# CAN_Wake_Up.net
KiCad netlist of a schematic drawn in EAGLE
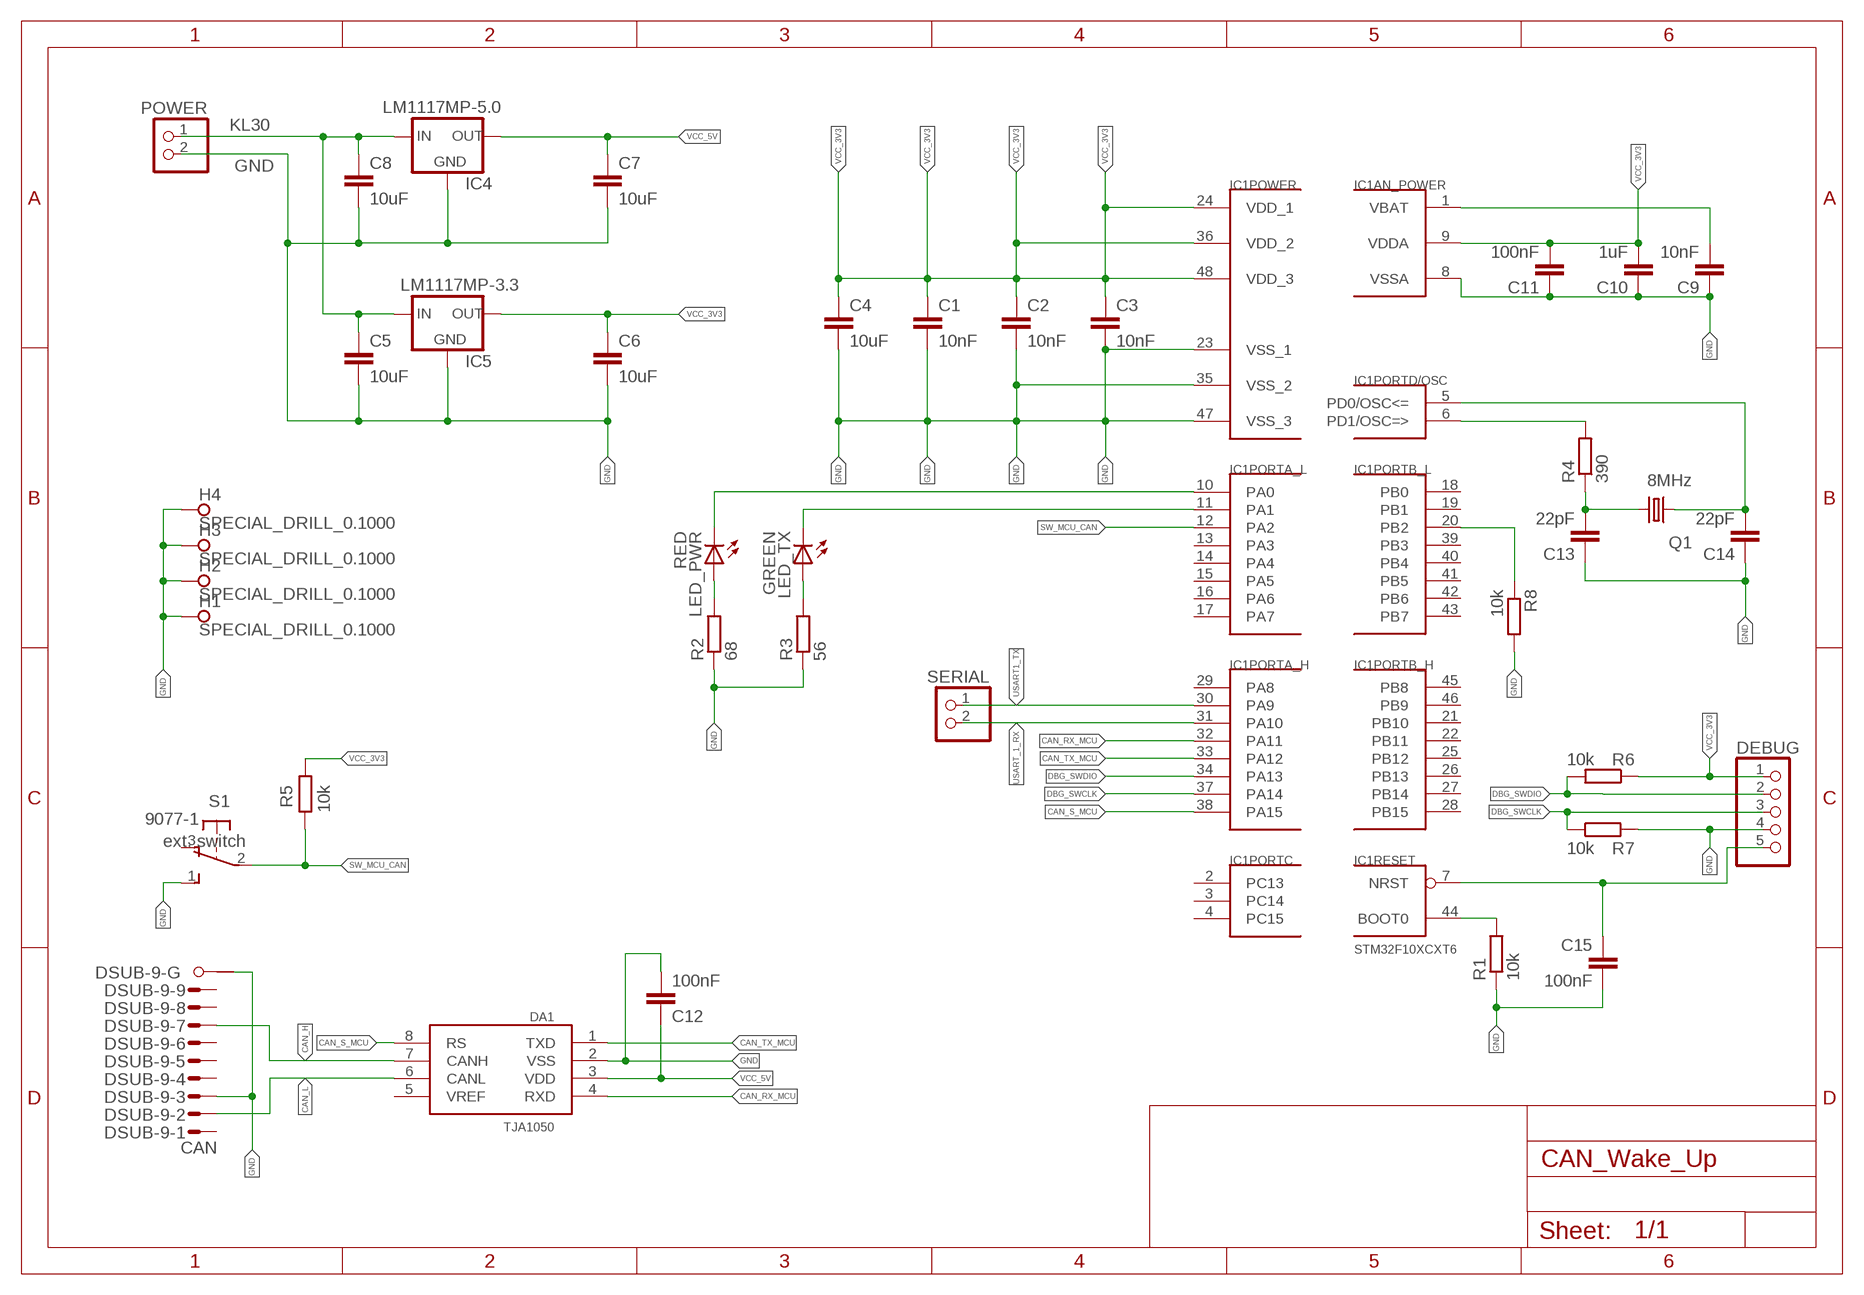
[diagram p0: schematic, sheet 1]

(export (version "E")
  (design (tool "Eeschema 10.0.6"))
  (components
    (comp (ref "C1")
      (value "10nF")
      (footprint "eagle-import:C0805")
      (libsource (lib "eagle-import") (part "C-EUC0805"))
    )
    (comp (ref "C2")
      (value "10nF")
      (footprint "eagle-import:C0805")
      (libsource (lib "eagle-import") (part "C-EUC0805"))
    )
    (comp (ref "C3")
      (value "10nF")
      (footprint "eagle-import:C0805")
      (libsource (lib "eagle-import") (part "C-EUC0805"))
    )
    (comp (ref "C4")
      (value "10uF")
      (footprint "eagle-import:C0805")
      (libsource (lib "eagle-import") (part "C-EUC0805"))
    )
    (comp (ref "C5")
      (value "10uF")
      (footprint "eagle-import:C0805")
      (libsource (lib "eagle-import") (part "C-EUC0805"))
    )
    (comp (ref "C6")
      (value "10uF")
      (footprint "eagle-import:C0805")
      (libsource (lib "eagle-import") (part "C-EUC0805"))
    )
    (comp (ref "C7")
      (value "10uF")
      (footprint "eagle-import:C0805")
      (libsource (lib "eagle-import") (part "C-EUC0805"))
    )
    (comp (ref "C8")
      (value "10uF")
      (footprint "eagle-import:C0805")
      (libsource (lib "eagle-import") (part "C-EUC0805"))
    )
    (comp (ref "C9")
      (value "10nF")
      (footprint "eagle-import:C0805")
      (libsource (lib "eagle-import") (part "C-EUC0805"))
    )
    (comp (ref "C10")
      (value "1uF")
      (footprint "eagle-import:C0805")
      (libsource (lib "eagle-import") (part "C-EUC0805"))
    )
    (comp (ref "C11")
      (value "100nF")
      (footprint "eagle-import:C0805")
      (libsource (lib "eagle-import") (part "C-EUC0805"))
    )
    (comp (ref "C12")
      (value "100nF")
      (footprint "eagle-import:C0805")
      (libsource (lib "eagle-import") (part "C-EUC0805"))
    )
    (comp (ref "C13")
      (value "22pF")
      (footprint "eagle-import:C0805")
      (libsource (lib "eagle-import") (part "C-EUC0805"))
    )
    (comp (ref "C14")
      (value "22pF")
      (footprint "eagle-import:C0805")
      (libsource (lib "eagle-import") (part "C-EUC0805"))
    )
    (comp (ref "C15")
      (value "100nF")
      (footprint "eagle-import:C0805")
      (libsource (lib "eagle-import") (part "C-EUC0805"))
    )
    (comp (ref "DA1")
      (value "TJA1050")
      (footprint "eagle-import:SO08")
      (libsource (lib "eagle-import") (part "TJA1050"))
    )
    (comp (ref "DEBUG")
      (value "PINHD-1X5")
      (footprint "eagle-import:1X05")
      (libsource (lib "eagle-import") (part "PINHD-1X5"))
    )
    (comp (ref "DSUB-9")
      (value "CAN")
      (footprint "eagle-import:M09HP")
      (libsource (lib "eagle-import") (part "M09HPS"))
    )
    (comp (ref "H1")
      (value "SPECIAL_DRILL_0.1000")
      (footprint "eagle-import:PAD_0.1000")
      (libsource (lib "eagle-import") (part "SPECIAL_DRILL_0.1000"))
    )
    (comp (ref "H2")
      (value "SPECIAL_DRILL_0.1000")
      (footprint "eagle-import:PAD_0.1000")
      (libsource (lib "eagle-import") (part "SPECIAL_DRILL_0.1000"))
    )
    (comp (ref "H3")
      (value "SPECIAL_DRILL_0.1000")
      (footprint "eagle-import:PAD_0.1000")
      (libsource (lib "eagle-import") (part "SPECIAL_DRILL_0.1000"))
    )
    (comp (ref "H4")
      (value "SPECIAL_DRILL_0.1000")
      (footprint "eagle-import:PAD_0.1000")
      (libsource (lib "eagle-import") (part "SPECIAL_DRILL_0.1000"))
    )
    (comp (ref "IC1")
      (value "STM32F10XCXT6")
      (footprint "eagle-import:TQFP48")
      (libsource (lib "eagle-import") (part "STM32F10XCXT6"))
    )
    (comp (ref "IC4")
      (value "LM1117MP-5.0")
      (footprint "eagle-import:SOT223")
      (fields (field (name "MF") "Texas Instruments"))
      (libsource (lib "eagle-import") (part "LM1117?-MP5.0"))
    )
    (comp (ref "IC5")
      (value "LM1117MP-3.3")
      (footprint "eagle-import:SOT223")
      (fields (field (name "MF") "Texas Instruments"))
      (libsource (lib "eagle-import") (part "LM1117?-MP3.3"))
    )
    (comp (ref "LED_PWR")
      (value "RED")
      (footprint "eagle-import:SML0805")
      (libsource (lib "eagle-import") (part "LEDSML0805"))
    )
    (comp (ref "LED_TX")
      (value "GREEN")
      (footprint "eagle-import:SML0805")
      (libsource (lib "eagle-import") (part "LEDSML0805"))
    )
    (comp (ref "POWER")
      (value "PINHD-1X2")
      (footprint "eagle-import:1X02")
      (libsource (lib "eagle-import") (part "PINHD-1X2"))
    )
    (comp (ref "Q1")
      (value "8MHz")
      (footprint "eagle-import:HC49UP")
      (libsource (lib "eagle-import") (part "CRYSTALHC49UP"))
    )
    (comp (ref "R1")
      (value "10k")
      (footprint "eagle-import:R0805")
      (libsource (lib "eagle-import") (part "R-EU_R0805"))
    )
    (comp (ref "R2")
      (value "68")
      (footprint "eagle-import:R0805")
      (libsource (lib "eagle-import") (part "R-EU_R0805"))
    )
    (comp (ref "R3")
      (value "56")
      (footprint "eagle-import:R0805")
      (libsource (lib "eagle-import") (part "R-EU_R0805"))
    )
    (comp (ref "R4")
      (value "390")
      (footprint "eagle-import:R0805")
      (libsource (lib "eagle-import") (part "R-EU_R0805"))
    )
    (comp (ref "R5")
      (value "10k")
      (footprint "eagle-import:R0805")
      (libsource (lib "eagle-import") (part "R-EU_R0805"))
    )
    (comp (ref "R6")
      (value "10k")
      (footprint "eagle-import:R0805")
      (libsource (lib "eagle-import") (part "R-EU_R0805"))
    )
    (comp (ref "R7")
      (value "10k")
      (footprint "eagle-import:R0805")
      (libsource (lib "eagle-import") (part "R-EU_R0805"))
    )
    (comp (ref "R8")
      (value "10k")
      (footprint "eagle-import:R0805")
      (libsource (lib "eagle-import") (part "R-EU_R0805"))
    )
    (comp (ref "S1")
      (value "9077-1")
      (footprint "eagle-import:9077-1")
      (libsource (lib "eagle-import") (part "9077-1"))
    )
    (comp (ref "SERIAL")
      (value "PINHD-1X2")
      (footprint "eagle-import:1X02")
      (libsource (lib "eagle-import") (part "PINHD-1X2"))
    )
  )
  (nets
    (net (code "1") (name "/KL30") (class "Default")
      (node (ref "C5") (pin "1") (pinfunction "1_1") (pintype "passive"))
      (node (ref "C8") (pin "1") (pinfunction "1_1") (pintype "passive"))
      (node (ref "IC4") (pin "3") (pinfunction "IN_3") (pintype "input"))
      (node (ref "IC5") (pin "3") (pinfunction "IN_3") (pintype "input"))
      (node (ref "POWER") (pin "1") (pinfunction "1_1") (pintype "passive"))
    )
    (net (code "2") (name "CAN_H") (class "Default")
      (node (ref "DA1") (pin "7") (pinfunction "CANH_7") (pintype "bidirectional"))
      (node (ref "DSUB-9") (pin "7") (pinfunction "M_7") (pintype "passive"))
    )
    (net (code "3") (name "CAN_L") (class "Default")
      (node (ref "DA1") (pin "6") (pinfunction "CANL_6") (pintype "bidirectional"))
      (node (ref "DSUB-9") (pin "2") (pinfunction "M_2") (pintype "passive"))
    )
    (net (code "4") (name "CAN_RX_MCU") (class "Default")
      (node (ref "DA1") (pin "4") (pinfunction "RXD_4") (pintype "output"))
      (node (ref "IC1") (pin "32") (pinfunction "PA11_32") (pintype "bidirectional"))
    )
    (net (code "5") (name "CAN_S_MCU") (class "Default")
      (node (ref "DA1") (pin "8") (pinfunction "RS_8") (pintype "input"))
      (node (ref "IC1") (pin "38") (pinfunction "PA15_38") (pintype "bidirectional"))
    )
    (net (code "6") (name "CAN_TX_MCU") (class "Default")
      (node (ref "DA1") (pin "1") (pinfunction "TXD_1") (pintype "input"))
      (node (ref "IC1") (pin "33") (pinfunction "PA12_33") (pintype "bidirectional"))
    )
    (net (code "7") (name "DBG_SWCLK") (class "Default")
      (node (ref "DEBUG") (pin "3") (pinfunction "3_3") (pintype "passive"))
      (node (ref "IC1") (pin "37") (pinfunction "PA14_37") (pintype "bidirectional"))
      (node (ref "R7") (pin "1") (pinfunction "1_1") (pintype "passive"))
    )
    (net (code "8") (name "DBG_SWDIO") (class "Default")
      (node (ref "DEBUG") (pin "2") (pinfunction "2_2") (pintype "passive"))
      (node (ref "IC1") (pin "34") (pinfunction "PA13_34") (pintype "bidirectional"))
      (node (ref "R6") (pin "2") (pinfunction "2_2") (pintype "passive"))
    )
    (net (code "9") (name "GND") (class "Default")
      (node (ref "C1") (pin "2") (pinfunction "2_2") (pintype "passive"))
      (node (ref "C10") (pin "1") (pinfunction "1_1") (pintype "passive"))
      (node (ref "C11") (pin "1") (pinfunction "1_1") (pintype "passive"))
      (node (ref "C12") (pin "2") (pinfunction "2_2") (pintype "passive"))
      (node (ref "C13") (pin "1") (pinfunction "1_1") (pintype "passive"))
      (node (ref "C14") (pin "1") (pinfunction "1_1") (pintype "passive"))
      (node (ref "C15") (pin "2") (pinfunction "2_2") (pintype "passive"))
      (node (ref "C2") (pin "2") (pinfunction "2_2") (pintype "passive"))
      (node (ref "C3") (pin "2") (pinfunction "2_2") (pintype "passive"))
      (node (ref "C4") (pin "2") (pinfunction "2_2") (pintype "passive"))
      (node (ref "C5") (pin "2") (pinfunction "2_2") (pintype "passive"))
      (node (ref "C6") (pin "2") (pinfunction "2_2") (pintype "passive"))
      (node (ref "C7") (pin "2") (pinfunction "2_2") (pintype "passive"))
      (node (ref "C8") (pin "2") (pinfunction "2_2") (pintype "passive"))
      (node (ref "C9") (pin "1") (pinfunction "1_1") (pintype "passive"))
      (node (ref "DA1") (pin "2") (pinfunction "VSS_2") (pintype "power_in"))
      (node (ref "DEBUG") (pin "4") (pinfunction "4_4") (pintype "passive"))
      (node (ref "DSUB-9") (pin "3") (pinfunction "M_3") (pintype "passive"))
      (node (ref "DSUB-9") (pin "G1") (pinfunction "G1_G1") (pintype "passive"))
      (node (ref "H1") (pin "1") (pinfunction "1_1") (pintype "passive"))
      (node (ref "H2") (pin "1") (pinfunction "1_1") (pintype "passive"))
      (node (ref "H3") (pin "1") (pinfunction "1_1") (pintype "passive"))
      (node (ref "H4") (pin "1") (pinfunction "1_1") (pintype "passive"))
      (node (ref "IC1") (pin "23") (pinfunction "VSS_1_23") (pintype "power_in"))
      (node (ref "IC1") (pin "35") (pinfunction "VSS_2_35") (pintype "power_in"))
      (node (ref "IC1") (pin "47") (pinfunction "VSS_3_47") (pintype "power_in"))
      (node (ref "IC1") (pin "8") (pinfunction "VSSA_8") (pintype "power_in"))
      (node (ref "IC4") (pin "1") (pinfunction "GND_1") (pintype "input"))
      (node (ref "IC5") (pin "1") (pinfunction "GND_1") (pintype "input"))
      (node (ref "POWER") (pin "2") (pinfunction "2_2") (pintype "passive"))
      (node (ref "R1") (pin "1") (pinfunction "1_1") (pintype "passive"))
      (node (ref "R2") (pin "1") (pinfunction "1_1") (pintype "passive"))
      (node (ref "R3") (pin "1") (pinfunction "1_1") (pintype "passive"))
      (node (ref "R7") (pin "2") (pinfunction "2_2") (pintype "passive"))
      (node (ref "R8") (pin "2") (pinfunction "2_2") (pintype "passive"))
      (node (ref "S1") (pin "1") (pinfunction "S_1") (pintype "passive"))
    )
    (net (code "10") (name "Net-(C13-Pad2)") (class "Default")
      (node (ref "C13") (pin "2") (pinfunction "2_2") (pintype "passive"))
      (node (ref "Q1") (pin "2") (pinfunction "2_2") (pintype "passive"))
      (node (ref "R4") (pin "1") (pinfunction "1_1") (pintype "passive"))
    )
    (net (code "11") (name "Net-(IC1A-VBAT)") (class "Default")
      (node (ref "C9") (pin "2") (pinfunction "2_2") (pintype "passive"))
      (node (ref "IC1") (pin "1") (pinfunction "VBAT_1") (pintype "power_in"))
    )
    (net (code "12") (name "Net-(IC1C-PA0)") (class "Default")
      (node (ref "IC1") (pin "10") (pinfunction "PA0_10") (pintype "bidirectional"))
      (node (ref "LED_PWR") (pin "C") (pinfunction "C_C") (pintype "passive"))
    )
    (net (code "13") (name "Net-(IC1C-PA1)") (class "Default")
      (node (ref "IC1") (pin "11") (pinfunction "PA1_11") (pintype "bidirectional"))
      (node (ref "LED_TX") (pin "C") (pinfunction "C_C") (pintype "passive"))
    )
    (net (code "14") (name "Net-(IC1E-PB2)") (class "Default")
      (node (ref "IC1") (pin "20") (pinfunction "PB2_20") (pintype "bidirectional"))
      (node (ref "R8") (pin "1") (pinfunction "1_1") (pintype "passive"))
    )
    (net (code "15") (name "Net-(IC1G-PD0{slash}OSC<=)") (class "Default")
      (node (ref "C14") (pin "2") (pinfunction "2_2") (pintype "passive"))
      (node (ref "IC1") (pin "5") (pinfunction "PD0/OSC<=_5") (pintype "bidirectional"))
      (node (ref "Q1") (pin "1") (pinfunction "1_1") (pintype "passive"))
    )
    (net (code "16") (name "Net-(IC1G-PD1{slash}OSC=>)") (class "Default")
      (node (ref "IC1") (pin "6") (pinfunction "PD1/OSC=>_6") (pintype "bidirectional"))
      (node (ref "R4") (pin "2") (pinfunction "2_2") (pintype "passive"))
    )
    (net (code "17") (name "Net-(IC1I-BOOT0)") (class "Default")
      (node (ref "IC1") (pin "44") (pinfunction "BOOT0_44") (pintype "input"))
      (node (ref "R1") (pin "2") (pinfunction "2_2") (pintype "passive"))
    )
    (net (code "18") (name "Net-(IC1I-NRST)") (class "Default")
      (node (ref "C15") (pin "1") (pinfunction "1_1") (pintype "passive"))
      (node (ref "DEBUG") (pin "5") (pinfunction "5_5") (pintype "passive"))
      (node (ref "IC1") (pin "7") (pinfunction "NRST_7") (pintype "input"))
    )
    (net (code "19") (name "Net-(LED_PWR-PadA)") (class "Default")
      (node (ref "LED_PWR") (pin "A") (pinfunction "A_A") (pintype "passive"))
      (node (ref "R2") (pin "2") (pinfunction "2_2") (pintype "passive"))
    )
    (net (code "20") (name "Net-(LED_TX-PadA)") (class "Default")
      (node (ref "LED_TX") (pin "A") (pinfunction "A_A") (pintype "passive"))
      (node (ref "R3") (pin "2") (pinfunction "2_2") (pintype "passive"))
    )
    (net (code "21") (name "SW_MCU_CAN") (class "Default")
      (node (ref "IC1") (pin "12") (pinfunction "PA2_12") (pintype "bidirectional"))
      (node (ref "R5") (pin "1") (pinfunction "1_1") (pintype "passive"))
      (node (ref "S1") (pin "2") (pinfunction "P_2") (pintype "passive"))
    )
    (net (code "22") (name "USART1_TX") (class "Default")
      (node (ref "IC1") (pin "30") (pinfunction "PA9_30") (pintype "bidirectional"))
      (node (ref "SERIAL") (pin "1") (pinfunction "1_1") (pintype "passive"))
    )
    (net (code "23") (name "USART_1_RX") (class "Default")
      (node (ref "IC1") (pin "31") (pinfunction "PA10_31") (pintype "bidirectional"))
      (node (ref "SERIAL") (pin "2") (pinfunction "2_2") (pintype "passive"))
    )
    (net (code "24") (name "VCC_3V3") (class "Default")
      (node (ref "C1") (pin "1") (pinfunction "1_1") (pintype "passive"))
      (node (ref "C10") (pin "2") (pinfunction "2_2") (pintype "passive"))
      (node (ref "C11") (pin "2") (pinfunction "2_2") (pintype "passive"))
      (node (ref "C2") (pin "1") (pinfunction "1_1") (pintype "passive"))
      (node (ref "C3") (pin "1") (pinfunction "1_1") (pintype "passive"))
      (node (ref "C4") (pin "1") (pinfunction "1_1") (pintype "passive"))
      (node (ref "C6") (pin "1") (pinfunction "1_1") (pintype "passive"))
      (node (ref "DEBUG") (pin "1") (pinfunction "1_1") (pintype "passive"))
      (node (ref "IC1") (pin "24") (pinfunction "VDD_1_24") (pintype "power_in"))
      (node (ref "IC1") (pin "36") (pinfunction "VDD_2_36") (pintype "power_in"))
      (node (ref "IC1") (pin "48") (pinfunction "VDD_3_48") (pintype "power_in"))
      (node (ref "IC1") (pin "9") (pinfunction "VDDA_9") (pintype "power_in"))
      (node (ref "IC5") (pin "2") (pinfunction "OUT_2") (pintype "passive"))
      (node (ref "IC5") (pin "4") (pinfunction "OUT_4") (pintype "passive"))
      (node (ref "R5") (pin "2") (pinfunction "2_2") (pintype "passive"))
      (node (ref "R6") (pin "1") (pinfunction "1_1") (pintype "passive"))
    )
    (net (code "25") (name "VCC_5V") (class "Default")
      (node (ref "C12") (pin "1") (pinfunction "1_1") (pintype "passive"))
      (node (ref "C7") (pin "1") (pinfunction "1_1") (pintype "passive"))
      (node (ref "DA1") (pin "3") (pinfunction "VDD_3") (pintype "power_in"))
      (node (ref "IC4") (pin "2") (pinfunction "OUT_2") (pintype "passive"))
      (node (ref "IC4") (pin "4") (pinfunction "OUT_4") (pintype "passive"))
    )
    (net (code "26") (name "unconnected-(DA1-VREF-Pad5)") (class "Default")
      (node (ref "DA1") (pin "5") (pinfunction "VREF_5") (pintype "passive"))
    )
    (net (code "27") (name "unconnected-(DSUB-9-PadG2)") (class "Default")
      (node (ref "DSUB-9") (pin "G2") (pinfunction "G2_G2") (pintype "passive"))
    )
    (net (code "28") (name "unconnected-(DSUB-9A-M-Pad1)") (class "Default")
      (node (ref "DSUB-9") (pin "1") (pinfunction "M_1") (pintype "passive"))
    )
    (net (code "29") (name "unconnected-(DSUB-9D-M-Pad4)") (class "Default")
      (node (ref "DSUB-9") (pin "4") (pinfunction "M_4") (pintype "passive"))
    )
    (net (code "30") (name "unconnected-(DSUB-9E-M-Pad5)") (class "Default")
      (node (ref "DSUB-9") (pin "5") (pinfunction "M_5") (pintype "passive"))
    )
    (net (code "31") (name "unconnected-(DSUB-9F-M-Pad6)") (class "Default")
      (node (ref "DSUB-9") (pin "6") (pinfunction "M_6") (pintype "passive"))
    )
    (net (code "32") (name "unconnected-(DSUB-9H-M-Pad8)") (class "Default")
      (node (ref "DSUB-9") (pin "8") (pinfunction "M_8") (pintype "passive"))
    )
    (net (code "33") (name "unconnected-(DSUB-9I-M-Pad9)") (class "Default")
      (node (ref "DSUB-9") (pin "9") (pinfunction "M_9") (pintype "passive"))
    )
    (net (code "34") (name "unconnected-(IC1B-PA8-Pad29)") (class "Default")
      (node (ref "IC1") (pin "29") (pinfunction "PA8_29") (pintype "bidirectional"))
    )
    (net (code "35") (name "unconnected-(IC1C-PA3-Pad13)") (class "Default")
      (node (ref "IC1") (pin "13") (pinfunction "PA3_13") (pintype "bidirectional"))
    )
    (net (code "36") (name "unconnected-(IC1C-PA4-Pad14)") (class "Default")
      (node (ref "IC1") (pin "14") (pinfunction "PA4_14") (pintype "bidirectional"))
    )
    (net (code "37") (name "unconnected-(IC1C-PA5-Pad15)") (class "Default")
      (node (ref "IC1") (pin "15") (pinfunction "PA5_15") (pintype "bidirectional"))
    )
    (net (code "38") (name "unconnected-(IC1C-PA6-Pad16)") (class "Default")
      (node (ref "IC1") (pin "16") (pinfunction "PA6_16") (pintype "bidirectional"))
    )
    (net (code "39") (name "unconnected-(IC1C-PA7-Pad17)") (class "Default")
      (node (ref "IC1") (pin "17") (pinfunction "PA7_17") (pintype "bidirectional"))
    )
    (net (code "40") (name "unconnected-(IC1D-PB8-Pad45)") (class "Default")
      (node (ref "IC1") (pin "45") (pinfunction "PB8_45") (pintype "bidirectional"))
    )
    (net (code "41") (name "unconnected-(IC1D-PB9-Pad46)") (class "Default")
      (node (ref "IC1") (pin "46") (pinfunction "PB9_46") (pintype "bidirectional"))
    )
    (net (code "42") (name "unconnected-(IC1D-PB10-Pad21)") (class "Default")
      (node (ref "IC1") (pin "21") (pinfunction "PB10_21") (pintype "bidirectional"))
    )
    (net (code "43") (name "unconnected-(IC1D-PB11-Pad22)") (class "Default")
      (node (ref "IC1") (pin "22") (pinfunction "PB11_22") (pintype "bidirectional"))
    )
    (net (code "44") (name "unconnected-(IC1D-PB12-Pad25)") (class "Default")
      (node (ref "IC1") (pin "25") (pinfunction "PB12_25") (pintype "bidirectional"))
    )
    (net (code "45") (name "unconnected-(IC1D-PB13-Pad26)") (class "Default")
      (node (ref "IC1") (pin "26") (pinfunction "PB13_26") (pintype "bidirectional"))
    )
    (net (code "46") (name "unconnected-(IC1D-PB14-Pad27)") (class "Default")
      (node (ref "IC1") (pin "27") (pinfunction "PB14_27") (pintype "bidirectional"))
    )
    (net (code "47") (name "unconnected-(IC1D-PB15-Pad28)") (class "Default")
      (node (ref "IC1") (pin "28") (pinfunction "PB15_28") (pintype "bidirectional"))
    )
    (net (code "48") (name "unconnected-(IC1E-PB0-Pad18)") (class "Default")
      (node (ref "IC1") (pin "18") (pinfunction "PB0_18") (pintype "bidirectional"))
    )
    (net (code "49") (name "unconnected-(IC1E-PB1-Pad19)") (class "Default")
      (node (ref "IC1") (pin "19") (pinfunction "PB1_19") (pintype "bidirectional"))
    )
    (net (code "50") (name "unconnected-(IC1E-PB3-Pad39)") (class "Default")
      (node (ref "IC1") (pin "39") (pinfunction "PB3_39") (pintype "bidirectional"))
    )
    (net (code "51") (name "unconnected-(IC1E-PB4-Pad40)") (class "Default")
      (node (ref "IC1") (pin "40") (pinfunction "PB4_40") (pintype "bidirectional"))
    )
    (net (code "52") (name "unconnected-(IC1E-PB5-Pad41)") (class "Default")
      (node (ref "IC1") (pin "41") (pinfunction "PB5_41") (pintype "bidirectional"))
    )
    (net (code "53") (name "unconnected-(IC1E-PB6-Pad42)") (class "Default")
      (node (ref "IC1") (pin "42") (pinfunction "PB6_42") (pintype "bidirectional"))
    )
    (net (code "54") (name "unconnected-(IC1E-PB7-Pad43)") (class "Default")
      (node (ref "IC1") (pin "43") (pinfunction "PB7_43") (pintype "bidirectional"))
    )
    (net (code "55") (name "unconnected-(IC1F-PC13-Pad2)") (class "Default")
      (node (ref "IC1") (pin "2") (pinfunction "PC13_2") (pintype "bidirectional"))
    )
    (net (code "56") (name "unconnected-(IC1F-PC14-Pad3)") (class "Default")
      (node (ref "IC1") (pin "3") (pinfunction "PC14_3") (pintype "bidirectional"))
    )
    (net (code "57") (name "unconnected-(IC1F-PC15-Pad4)") (class "Default")
      (node (ref "IC1") (pin "4") (pinfunction "PC15_4") (pintype "bidirectional"))
    )
    (net (code "58") (name "unconnected-(S1-O-Pad3)") (class "Default")
      (node (ref "S1") (pin "3") (pinfunction "O_3") (pintype "passive"))
    )
  )
)
